# tape_smd2.net
KiCad netlist of a schematic drawn in EAGLE
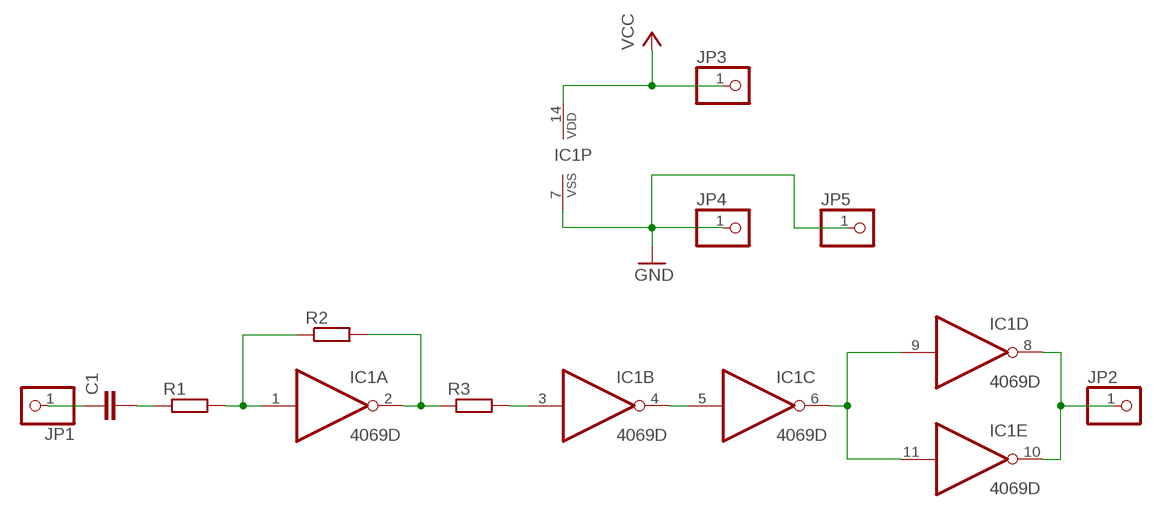
[diagram p0: schematic, sheet 1]

(export (version "E")
  (design (tool "Eeschema 10.0.6"))
  (components
    (comp (ref "C1")
      (value "C-EUC0805")
      (footprint "eagle-import:C0805")
      (libsource (lib "eagle-import") (part "C-EUC0805"))
    )
    (comp (ref "IC1")
      (value "4069D")
      (footprint "eagle-import:SO14")
      (libsource (lib "eagle-import") (part "4069D"))
    )
    (comp (ref "JP1")
      (value "PINHD-1X1")
      (footprint "eagle-import:1X01")
      (libsource (lib "eagle-import") (part "PINHD-1X1"))
    )
    (comp (ref "JP2")
      (value "PINHD-1X1")
      (footprint "eagle-import:1X01")
      (libsource (lib "eagle-import") (part "PINHD-1X1"))
    )
    (comp (ref "JP3")
      (value "PINHD-1X1")
      (footprint "eagle-import:1X01")
      (libsource (lib "eagle-import") (part "PINHD-1X1"))
    )
    (comp (ref "JP4")
      (value "PINHD-1X1")
      (footprint "eagle-import:1X01")
      (libsource (lib "eagle-import") (part "PINHD-1X1"))
    )
    (comp (ref "JP5")
      (value "PINHD-1X1")
      (footprint "eagle-import:1X01")
      (libsource (lib "eagle-import") (part "PINHD-1X1"))
    )
    (comp (ref "R1")
      (value "R-EU_R0805")
      (footprint "eagle-import:R0805")
      (libsource (lib "eagle-import") (part "R-EU_R0805"))
    )
    (comp (ref "R2")
      (value "R-EU_R0805")
      (footprint "eagle-import:R0805")
      (libsource (lib "eagle-import") (part "R-EU_R0805"))
    )
    (comp (ref "R3")
      (value "R-EU_R0805")
      (footprint "eagle-import:R0805")
      (libsource (lib "eagle-import") (part "R-EU_R0805"))
    )
  )
  (nets
    (net (code "1") (name "GND") (class "Default")
      (node (ref "IC1") (pin "7") (pinfunction "VSS_7") (pintype "power_in"))
      (node (ref "JP4") (pin "1") (pinfunction "1_1") (pintype "passive"))
      (node (ref "JP5") (pin "1") (pinfunction "1_1") (pintype "passive"))
    )
    (net (code "2") (name "Net-(C1-Pad1)") (class "Default")
      (node (ref "C1") (pin "1") (pinfunction "1_1") (pintype "passive"))
      (node (ref "JP1") (pin "1") (pinfunction "1_1") (pintype "passive"))
    )
    (net (code "3") (name "Net-(C1-Pad2)") (class "Default")
      (node (ref "C1") (pin "2") (pinfunction "2_2") (pintype "passive"))
      (node (ref "R1") (pin "1") (pinfunction "1_1") (pintype "passive"))
    )
    (net (code "4") (name "Net-(IC1A-I)") (class "Default")
      (node (ref "IC1") (pin "1") (pinfunction "I_1") (pintype "input"))
      (node (ref "R1") (pin "2") (pinfunction "2_2") (pintype "passive"))
      (node (ref "R2") (pin "1") (pinfunction "1_1") (pintype "passive"))
    )
    (net (code "5") (name "Net-(IC1A-O)") (class "Default")
      (node (ref "IC1") (pin "2") (pinfunction "O_2") (pintype "output"))
      (node (ref "R2") (pin "2") (pinfunction "2_2") (pintype "passive"))
      (node (ref "R3") (pin "1") (pinfunction "1_1") (pintype "passive"))
    )
    (net (code "6") (name "Net-(IC1B-I)") (class "Default")
      (node (ref "IC1") (pin "3") (pinfunction "I_3") (pintype "input"))
      (node (ref "R3") (pin "2") (pinfunction "2_2") (pintype "passive"))
    )
    (net (code "7") (name "Net-(IC1B-O)") (class "Default")
      (node (ref "IC1") (pin "4") (pinfunction "O_4") (pintype "output"))
      (node (ref "IC1") (pin "5") (pinfunction "I_5") (pintype "input"))
    )
    (net (code "8") (name "Net-(IC1C-O)") (class "Default")
      (node (ref "IC1") (pin "11") (pinfunction "I_11") (pintype "input"))
      (node (ref "IC1") (pin "6") (pinfunction "O_6") (pintype "output"))
      (node (ref "IC1") (pin "9") (pinfunction "I_9") (pintype "input"))
    )
    (net (code "9") (name "Net-(IC1D-O)") (class "Default")
      (node (ref "IC1") (pin "10") (pinfunction "O_10") (pintype "output"))
      (node (ref "IC1") (pin "8") (pinfunction "O_8") (pintype "output"))
      (node (ref "JP2") (pin "1") (pinfunction "1_1") (pintype "passive"))
    )
    (net (code "10") (name "VCC") (class "Default")
      (node (ref "IC1") (pin "14") (pinfunction "VDD_14") (pintype "power_in"))
      (node (ref "JP3") (pin "1") (pinfunction "1_1") (pintype "passive"))
    )
  )
)
